# TestLEDs.net
KiCad netlist of a schematic drawn in Altium Designer
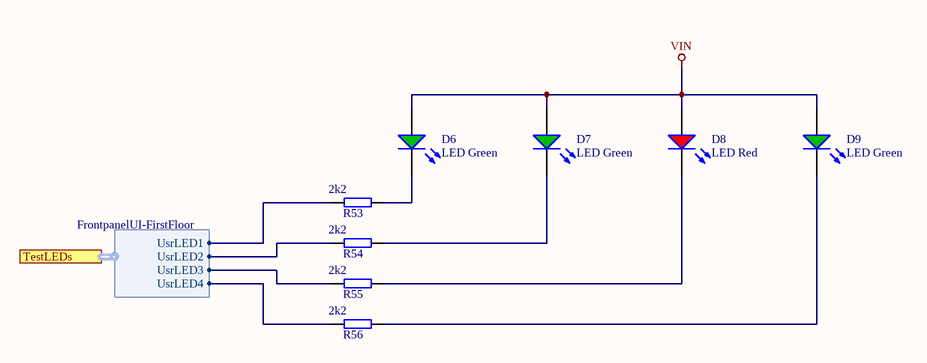
[diagram p0: TestLEDs.SchDoc]

(export (version "E")
  (design (tool "Eeschema 10.0.6"))
  (components
    (comp (ref "D6")
      (value "LED Green")
      (footprint "WL-SMCW_0603")
      (description "Standard LEDs - SMD 0603 green")
      (fields
        (field (name "MANUFACTURER PART NUMBER") "UZgen_LED_0603_Green")
        (field (name "MANUFACTURER") "UZgen")
        (field (name "CREATED FROM") "UZgenTool")
      )
      (libsource (lib "user") (part "LED_Green"))
    )
    (comp (ref "D7")
      (value "LED Green")
      (footprint "WL-SMCW_0603")
      (description "Standard LEDs - SMD 0603 green")
      (fields
        (field (name "MANUFACTURER PART NUMBER") "UZgen_LED_0603_Green")
        (field (name "MANUFACTURER") "UZgen")
        (field (name "CREATED FROM") "UZgenTool")
      )
      (libsource (lib "user") (part "LED_Green"))
    )
    (comp (ref "D8")
      (value "LED Red")
      (footprint "WL-SMCW_0603")
      (description "Standard LEDs - SMD 0603 red")
      (fields
        (field (name "MANUFACTURER PART NUMBER") "UZgen_LED_0603_Red")
        (field (name "MANUFACTURER") "UZgen")
        (field (name "CREATED FROM") "UZgenTool")
      )
      (libsource (lib "user") (part "LED_Red"))
    )
    (comp (ref "D9")
      (value "LED Green")
      (footprint "WL-SMCW_0603")
      (description "Standard LEDs - SMD 0603 green")
      (fields
        (field (name "MANUFACTURER PART NUMBER") "UZgen_LED_0603_Green")
        (field (name "MANUFACTURER") "UZgen")
        (field (name "CREATED FROM") "UZgenTool")
      )
      (libsource (lib "user") (part "LED_Green"))
    )
    (comp (ref "R53")
      (value "2k2")
      (footprint "R_1206_TE")
      (description "Generic resistor")
      (fields
        (field (name "MANUFACTURER PART NUMBER") "UZgen_R_1206_2k2")
        (field (name "MANUFACTURER") "UZgen")
        (field (name "CREATED FROM") "UZgenTool")
      )
      (libsource (lib "user") (part "RES"))
    )
    (comp (ref "R54")
      (value "2k2")
      (footprint "R_1206_TE")
      (description "Generic resistor")
      (fields
        (field (name "MANUFACTURER PART NUMBER") "UZgen_R_1206_2k2")
        (field (name "MANUFACTURER") "UZgen")
        (field (name "CREATED FROM") "UZgenTool")
      )
      (libsource (lib "user") (part "RES"))
    )
    (comp (ref "R55")
      (value "2k2")
      (footprint "R_1206_TE")
      (description "Generic resistor")
      (fields
        (field (name "MANUFACTURER PART NUMBER") "UZgen_R_1206_2k2")
        (field (name "MANUFACTURER") "UZgen")
        (field (name "CREATED FROM") "UZgenTool")
      )
      (libsource (lib "user") (part "RES"))
    )
    (comp (ref "R56")
      (value "2k2")
      (footprint "R_1206_TE")
      (description "Generic resistor")
      (fields
        (field (name "MANUFACTURER PART NUMBER") "UZgen_R_1206_2k2")
        (field (name "MANUFACTURER") "UZgen")
        (field (name "CREATED FROM") "UZgenTool")
      )
      (libsource (lib "user") (part "RES"))
    )
  )
  (nets
    (net (code "2") (name "/UsrLED1") (class "Default")
      (node (ref "R53") (pin "1") (pinfunction "1_1") (pintype "passive"))
    )
    (net (code "3") (name "/UsrLED2") (class "Default")
      (node (ref "R54") (pin "1") (pinfunction "1_1") (pintype "passive"))
    )
    (net (code "4") (name "/UsrLED3") (class "Default")
      (node (ref "R55") (pin "1") (pinfunction "1_1") (pintype "passive"))
    )
    (net (code "5") (name "/UsrLED4") (class "Default")
      (node (ref "R56") (pin "1") (pinfunction "1_1") (pintype "passive"))
    )
    (net (code "7") (name "Net-(D6-K)") (class "Default")
      (node (ref "D6") (pin "1") (pinfunction "K_1") (pintype "passive"))
      (node (ref "R53") (pin "2") (pinfunction "2_2") (pintype "passive"))
    )
    (net (code "8") (name "Net-(D7-K)") (class "Default")
      (node (ref "D7") (pin "1") (pinfunction "K_1") (pintype "passive"))
      (node (ref "R54") (pin "2") (pinfunction "2_2") (pintype "passive"))
    )
    (net (code "9") (name "Net-(D8-K)") (class "Default")
      (node (ref "D8") (pin "1") (pinfunction "K_1") (pintype "passive"))
      (node (ref "R55") (pin "2") (pinfunction "2_2") (pintype "passive"))
    )
    (net (code "10") (name "Net-(D9-K)") (class "Default")
      (node (ref "D9") (pin "1") (pinfunction "K_1") (pintype "passive"))
      (node (ref "R56") (pin "2") (pinfunction "2_2") (pintype "passive"))
    )
    (net (code "11") (name "VIN") (class "Default")
      (node (ref "D6") (pin "2") (pinfunction "A_2") (pintype "passive"))
      (node (ref "D7") (pin "2") (pinfunction "A_2") (pintype "passive"))
      (node (ref "D8") (pin "2") (pinfunction "A_2") (pintype "passive"))
      (node (ref "D9") (pin "2") (pinfunction "A_2") (pintype "passive"))
    )
  )
)
